# Loop_Schematic_r1_0_easyeda.net
KiCad netlist of a schematic drawn in EasyEDA
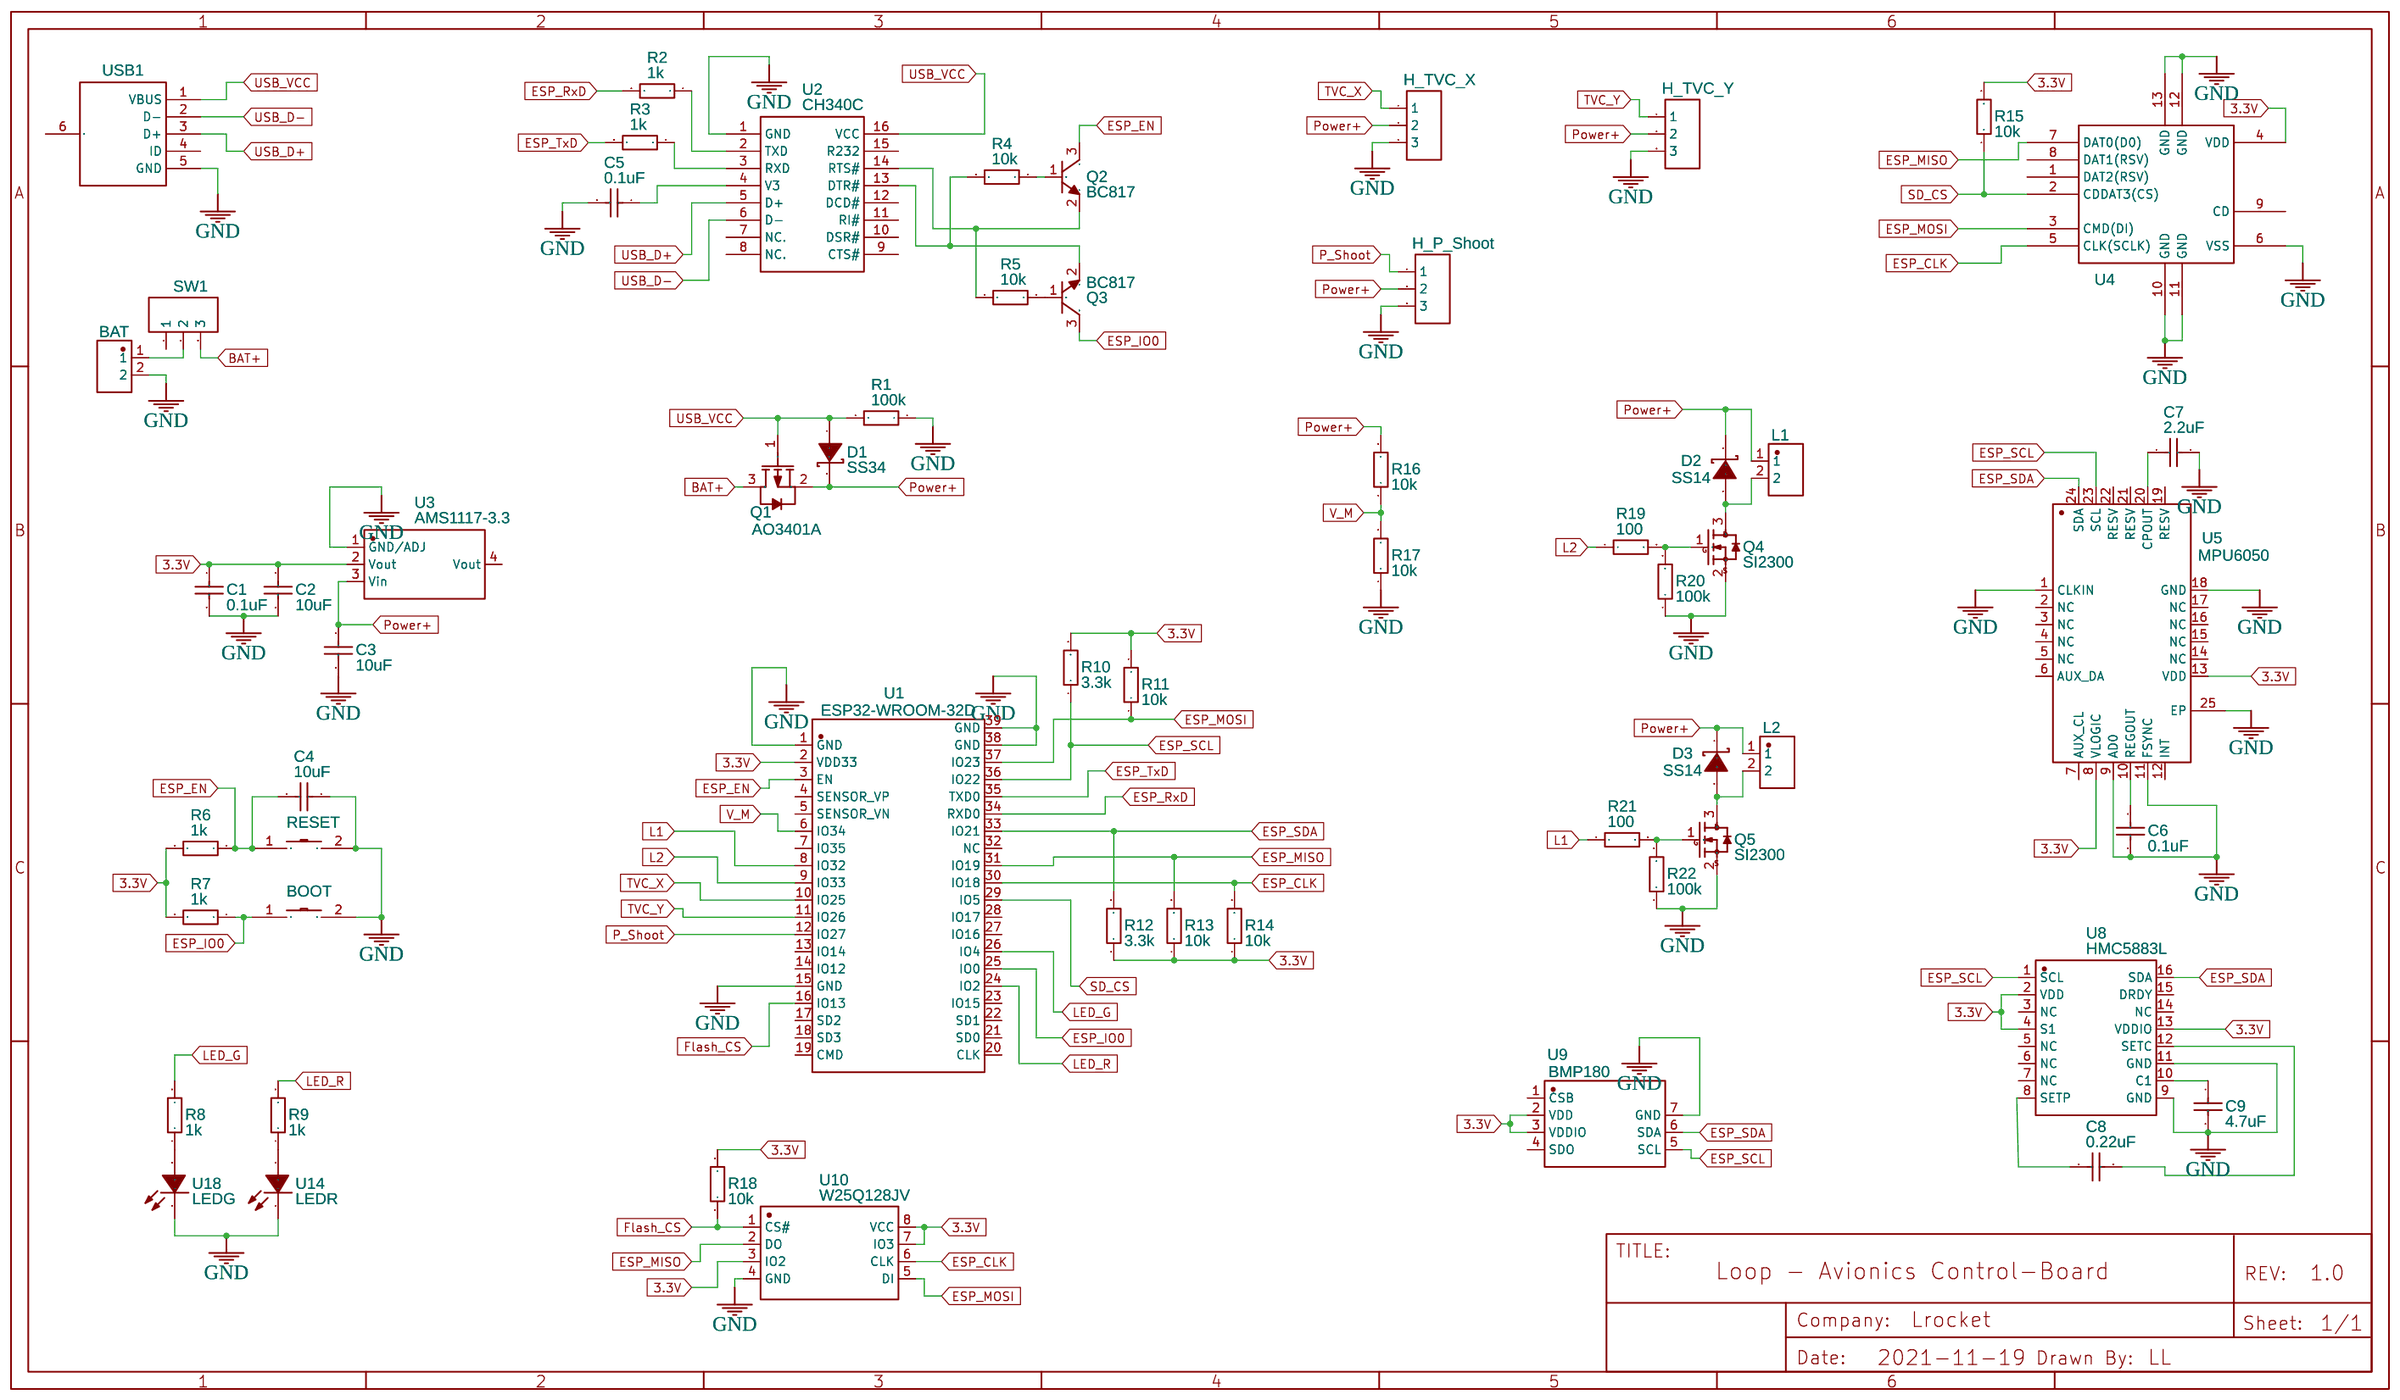
[diagram p0: schematic sheet]

(export (version "E")
  (design (tool "Eeschema 10.0.6"))
  (components
    (comp (ref "BAT")
      (value "BAT")
      (fields
        (field (name "BOM_Manufacturer Part") "KF128-5.08-2P")
        (field (name "BOM_Supplier Part") "C474952")
      )
      (libsource (lib "") (part "KF128-5.08-2P_1"))
    )
    (comp (ref "BOOT")
      (value "TS-1101-C-W")
      (fields (field (name "BOM_Supplier Part") "C318938"))
      (libsource (lib "") (part "TS-1101-C-W_1"))
    )
    (comp (ref "C1")
      (value "0.1uF")
      (fields
        (field (name "BOM_Manufacturer Part") "CC0603KRX7R9BB103")
        (field (name "BOM_Supplier Part") "C100042")
      )
      (libsource (lib "") (part "CC0603KRX7R9BB103"))
    )
    (comp (ref "C2")
      (value "10uF")
      (fields
        (field (name "BOM_Manufacturer Part") "CC0603KRX7R9BB103")
        (field (name "BOM_Supplier Part") "C100042")
      )
      (libsource (lib "") (part "CC0603KRX7R9BB103"))
    )
    (comp (ref "C3")
      (value "10uF")
      (fields
        (field (name "BOM_Manufacturer Part") "CC0603KRX7R9BB103")
        (field (name "BOM_Supplier Part") "C100042")
      )
      (libsource (lib "") (part "CC0603KRX7R9BB103"))
    )
    (comp (ref "C4")
      (value "10uF")
      (fields
        (field (name "BOM_Manufacturer Part") "CC0603KRX7R9BB103")
        (field (name "BOM_Supplier Part") "C100042")
      )
      (libsource (lib "") (part "CC0603KRX7R9BB103_1"))
    )
    (comp (ref "C5")
      (value "0.1uF")
      (fields
        (field (name "BOM_Manufacturer Part") "CC0603KRX7R9BB103")
        (field (name "BOM_Supplier Part") "C100042")
      )
      (libsource (lib "") (part "CC0603KRX7R9BB103_1"))
    )
    (comp (ref "C6")
      (value "0.1uF")
      (fields
        (field (name "BOM_Manufacturer Part") "CC0603KRX7R9BB103")
        (field (name "BOM_Supplier Part") "C100042")
      )
      (libsource (lib "") (part "CC0603KRX7R9BB103_2"))
    )
    (comp (ref "C7")
      (value "2.2uF")
      (fields
        (field (name "BOM_Manufacturer Part") "CC0603KRX7R9BB103")
        (field (name "BOM_Supplier Part") "C100042")
      )
      (libsource (lib "") (part "CC0603KRX7R9BB103_3"))
    )
    (comp (ref "C8")
      (value "0.22uF")
      (fields
        (field (name "BOM_Manufacturer Part") "CC0603KRX7R9BB103")
        (field (name "BOM_Supplier Part") "C100042")
      )
      (libsource (lib "") (part "CC0603KRX7R9BB103_3"))
    )
    (comp (ref "C9")
      (value "4.7uF")
      (fields
        (field (name "BOM_Manufacturer Part") "CC0603KRX7R9BB103")
        (field (name "BOM_Supplier Part") "C100042")
      )
      (libsource (lib "") (part "CC0603KRX7R9BB103"))
    )
    (comp (ref "D1")
      (value "SS34")
      (fields (field (name "BOM_Supplier Part") "C13763"))
      (libsource (lib "") (part "SS34"))
    )
    (comp (ref "D2")
      (value "SS14")
      (fields (field (name "BOM_Supplier Part") "C2480"))
      (libsource (lib "") (part "SS14"))
    )
    (comp (ref "D3")
      (value "SS14")
      (fields (field (name "BOM_Supplier Part") "C2480"))
      (libsource (lib "") (part "SS14"))
    )
    (comp (ref "L1")
      (value "L1")
      (fields
        (field (name "BOM_Manufacturer Part") "KF128-5.08-2P")
        (field (name "BOM_Supplier Part") "C474952")
      )
      (libsource (lib "") (part "KF128-5.08-2P"))
    )
    (comp (ref "L2")
      (value "KF128-5.08-2P")
      (fields (field (name "BOM_Supplier Part") "C474952"))
      (libsource (lib "") (part "KF128-5.08-2P"))
    )
    (comp (ref "P_SHOOT")
      (value "H_P_Shoot")
      (fields
        (field (name "BOM_Manufacturer Part") "Header2.54mm 1*3P")
        (field (name "BOM_Supplier Part") "C49257")
      )
      (libsource (lib "") (part "Header-Male-2.54_1x3"))
    )
    (comp (ref "Q1")
      (value "AO3401A")
      (fields (field (name "BOM_Supplier Part") "C15127"))
      (libsource (lib "") (part "AO3401A"))
    )
    (comp (ref "Q2")
      (value "BC817")
      (fields (field (name "BOM_Manufacturer Part") "BC817-25") (field (name "BOM_Supplier Part") "C8588"))
      (libsource (lib "") (part "BC817-25_1"))
    )
    (comp (ref "Q3")
      (value "BC817")
      (fields (field (name "BOM_Manufacturer Part") "BC817-25") (field (name "BOM_Supplier Part") "C8588"))
      (libsource (lib "") (part "BC817-25"))
    )
    (comp (ref "Q4")
      (value "SI2300")
      (fields (field (name "BOM_Supplier Part") "C181085"))
      (libsource (lib "") (part "SI2300"))
    )
    (comp (ref "Q5")
      (value "SI2300")
      (fields (field (name "BOM_Supplier Part") "C181085"))
      (libsource (lib "") (part "SI2300"))
    )
    (comp (ref "R1")
      (value "100k")
      (fields
        (field (name "BOM_Manufacturer Part") "TR0603B10KP05250.1W")
        (field (name "BOM_Supplier Part") "C188363")
      )
      (libsource (lib "") (part "TR0603B10KP05250.1W_1"))
    )
    (comp (ref "R2")
      (value "1k")
      (fields
        (field (name "BOM_Manufacturer Part") "TR0603B10KP05250.1W")
        (field (name "BOM_Supplier Part") "C188363")
      )
      (libsource (lib "") (part "TR0603B10KP05250.1W_1"))
    )
    (comp (ref "R3")
      (value "1k")
      (fields
        (field (name "BOM_Manufacturer Part") "TR0603B10KP05250.1W")
        (field (name "BOM_Supplier Part") "C188363")
      )
      (libsource (lib "") (part "TR0603B10KP05250.1W_1"))
    )
    (comp (ref "R4")
      (value "10k")
      (fields
        (field (name "BOM_Manufacturer Part") "TR0603B10KP05250.1W")
        (field (name "BOM_Supplier Part") "C188363")
      )
      (libsource (lib "") (part "TR0603B10KP05250.1W_1"))
    )
    (comp (ref "R5")
      (value "10k")
      (fields
        (field (name "BOM_Manufacturer Part") "TR0603B10KP05250.1W")
        (field (name "BOM_Supplier Part") "C188363")
      )
      (libsource (lib "") (part "TR0603B10KP05250.1W_1"))
    )
    (comp (ref "R6")
      (value "1k")
      (fields
        (field (name "BOM_Manufacturer Part") "TR0603B10KP05250.1W")
        (field (name "BOM_Supplier Part") "C188363")
      )
      (libsource (lib "") (part "TR0603B10KP05250.1W_1"))
    )
    (comp (ref "R7")
      (value "1k")
      (fields
        (field (name "BOM_Manufacturer Part") "TR0603B10KP05250.1W")
        (field (name "BOM_Supplier Part") "C188363")
      )
      (libsource (lib "") (part "TR0603B10KP05250.1W_1"))
    )
    (comp (ref "R8")
      (value "1k")
      (fields
        (field (name "BOM_Manufacturer Part") "TR0603B10KP05250.1W")
        (field (name "BOM_Supplier Part") "C188363")
      )
      (libsource (lib "") (part "TR0603B10KP05250.1W"))
    )
    (comp (ref "R9")
      (value "1k")
      (fields
        (field (name "BOM_Manufacturer Part") "TR0603B10KP05250.1W")
        (field (name "BOM_Supplier Part") "C188363")
      )
      (libsource (lib "") (part "TR0603B10KP05250.1W"))
    )
    (comp (ref "R10")
      (value "3.3k")
      (fields
        (field (name "BOM_Manufacturer Part") "TR0603B10KP05250.1W")
        (field (name "BOM_Supplier Part") "C188363")
      )
      (libsource (lib "") (part "TR0603B10KP05250.1W"))
    )
    (comp (ref "R11")
      (value "10k")
      (fields
        (field (name "BOM_Manufacturer Part") "TR0603B10KP05250.1W")
        (field (name "BOM_Supplier Part") "C188363")
      )
      (libsource (lib "") (part "TR0603B10KP05250.1W"))
    )
    (comp (ref "R12")
      (value "3.3k")
      (fields
        (field (name "BOM_Manufacturer Part") "TR0603B10KP05250.1W")
        (field (name "BOM_Supplier Part") "C188363")
      )
      (libsource (lib "") (part "TR0603B10KP05250.1W"))
    )
    (comp (ref "R13")
      (value "10k")
      (fields
        (field (name "BOM_Manufacturer Part") "TR0603B10KP05250.1W")
        (field (name "BOM_Supplier Part") "C188363")
      )
      (libsource (lib "") (part "TR0603B10KP05250.1W"))
    )
    (comp (ref "R14")
      (value "10k")
      (fields
        (field (name "BOM_Manufacturer Part") "TR0603B10KP05250.1W")
        (field (name "BOM_Supplier Part") "C188363")
      )
      (libsource (lib "") (part "TR0603B10KP05250.1W"))
    )
    (comp (ref "R15")
      (value "10k")
      (fields
        (field (name "BOM_Manufacturer Part") "TR0603B10KP05250.1W")
        (field (name "BOM_Supplier Part") "C188363")
      )
      (libsource (lib "") (part "TR0603B10KP05250.1W"))
    )
    (comp (ref "R16")
      (value "10k")
      (fields
        (field (name "BOM_Manufacturer Part") "TR0603B10KP05250.1W")
        (field (name "BOM_Supplier Part") "C188363")
      )
      (libsource (lib "") (part "TR0603B10KP05250.1W"))
    )
    (comp (ref "R17")
      (value "10k")
      (fields
        (field (name "BOM_Manufacturer Part") "TR0603B10KP05250.1W")
        (field (name "BOM_Supplier Part") "C188363")
      )
      (libsource (lib "") (part "TR0603B10KP05250.1W"))
    )
    (comp (ref "R18")
      (value "10k")
      (fields
        (field (name "BOM_Manufacturer Part") "TR0603B10KP05250.1W")
        (field (name "BOM_Supplier Part") "C188363")
      )
      (libsource (lib "") (part "TR0603B10KP05250.1W"))
    )
    (comp (ref "R19")
      (value "100")
      (fields
        (field (name "BOM_Manufacturer Part") "TR0603B10KP05250.1W")
        (field (name "BOM_Supplier Part") "C188363")
      )
      (libsource (lib "") (part "TR0603B10KP05250.1W_2"))
    )
    (comp (ref "R20")
      (value "100k")
      (fields
        (field (name "BOM_Manufacturer Part") "TR0603B10KP05250.1W")
        (field (name "BOM_Supplier Part") "C188363")
      )
      (libsource (lib "") (part "TR0603B10KP05250.1W"))
    )
    (comp (ref "R21")
      (value "100")
      (fields
        (field (name "BOM_Manufacturer Part") "TR0603B10KP05250.1W")
        (field (name "BOM_Supplier Part") "C188363")
      )
      (libsource (lib "") (part "TR0603B10KP05250.1W_2"))
    )
    (comp (ref "R22")
      (value "100k")
      (fields
        (field (name "BOM_Manufacturer Part") "TR0603B10KP05250.1W")
        (field (name "BOM_Supplier Part") "C188363")
      )
      (libsource (lib "") (part "TR0603B10KP05250.1W"))
    )
    (comp (ref "RESET")
      (value "TS-1101-C-W")
      (fields (field (name "BOM_Supplier Part") "C318938"))
      (libsource (lib "") (part "TS-1101-C-W"))
    )
    (comp (ref "SW1")
      (value "SW1")
      (fields
        (field (name "BOM_Manufacturer Part") "Header2.54mm 1*3P")
        (field (name "BOM_Supplier Part") "C49257")
      )
      (libsource (lib "") (part "Header-Male-2.54_1x3_1"))
    )
    (comp (ref "TVC_X")
      (value "H_TVC_X")
      (fields
        (field (name "BOM_Manufacturer Part") "Header2.54mm 1*3P")
        (field (name "BOM_Supplier Part") "C49257")
      )
      (libsource (lib "") (part "Header-Male-2.54_1x3_2"))
    )
    (comp (ref "TVC_Y")
      (value "H_TVC_Y")
      (fields
        (field (name "BOM_Manufacturer Part") "Header2.54mm 1*3P")
        (field (name "BOM_Supplier Part") "C49257")
      )
      (libsource (lib "") (part "Header-Male-2.54_1x3_3"))
    )
    (comp (ref "U1")
      (value "ESP32-WROOM-32D")
      (fields (field (name "BOM_Supplier Part") "C473012"))
      (libsource (lib "") (part "ESP32-WROOM-32D"))
    )
    (comp (ref "U2")
      (value "CH340C")
      (fields (field (name "BOM_Supplier Part") "C84681"))
      (libsource (lib "") (part "CH340C"))
    )
    (comp (ref "U3")
      (value "AMS1117-3.3")
      (fields (field (name "BOM_Supplier Part") "C6186"))
      (libsource (lib "") (part "AMS1117-3.3"))
    )
    (comp (ref "U4")
      (value "TF-01A")
      (fields (field (name "BOM_Supplier Part") "C91145"))
      (libsource (lib "") (part "TF-01A"))
    )
    (comp (ref "U5")
      (value "MPU6050")
      (fields
        (field (name "BOM_Manufacturer Part") "MPU6050-YJLTY")
        (field (name "BOM_Supplier Part") "C2912107")
      )
      (libsource (lib "") (part "MPU6050-YJLTY"))
    )
    (comp (ref "U8")
      (value "HMC5883L")
      (fields (field (name "BOM_Supplier Part") "C2859540"))
      (libsource (lib "") (part "HMC5883L"))
    )
    (comp (ref "U9")
      (value "BMP180")
      (fields (field (name "BOM_Supplier Part") "C438474"))
      (libsource (lib "") (part "BMP180"))
    )
    (comp (ref "U10")
      (value "W25Q128JV")
      (fields
        (field (name "BOM_Manufacturer Part") "W25Q128JVSIQTR")
        (field (name "BOM_Supplier Part") "C97521")
      )
      (libsource (lib "") (part "W25Q128JVSIQTR"))
    )
    (comp (ref "U14")
      (value "LEDR")
      (fields (field (name "BOM_Manufacturer Part") "SZYY0603W") (field (name "BOM_Supplier Part") "C434422"))
      (libsource (lib "") (part "SZYY0603W"))
    )
    (comp (ref "U18")
      (value "LEDG")
      (fields (field (name "BOM_Manufacturer Part") "SZYY0603W") (field (name "BOM_Supplier Part") "C434422"))
      (libsource (lib "") (part "SZYY0603W"))
    )
    (comp (ref "USB1")
      (value "USB1")
      (fields
        (field (name "BOM_Manufacturer Part") "U254-051T-4BH83-S1S")
        (field (name "BOM_Supplier Part") "C319160")
      )
      (libsource (lib "") (part "U254-051T-4BH83-S1S"))
    )
  )
  (nets
    (net (code "1") (name "3.3V") (class "Default")
      (node (ref "C1") (pin "1") (pinfunction "1_1") (pintype "input"))
      (node (ref "C2") (pin "1") (pinfunction "1_1") (pintype "input"))
      (node (ref "R10") (pin "2") (pinfunction "2_2") (pintype "unspecified"))
      (node (ref "R11") (pin "2") (pinfunction "2_2") (pintype "unspecified"))
      (node (ref "R12") (pin "1") (pinfunction "1_1") (pintype "unspecified"))
      (node (ref "R13") (pin "1") (pinfunction "1_1") (pintype "unspecified"))
      (node (ref "R14") (pin "1") (pinfunction "1_1") (pintype "unspecified"))
      (node (ref "R15") (pin "2") (pinfunction "2_2") (pintype "unspecified"))
      (node (ref "R18") (pin "2") (pinfunction "2_2") (pintype "unspecified"))
      (node (ref "R6") (pin "2") (pinfunction "2_2") (pintype "unspecified"))
      (node (ref "R7") (pin "2") (pinfunction "2_2") (pintype "unspecified"))
      (node (ref "U1") (pin "2") (pinfunction "VDD33_2") (pintype "unspecified"))
      (node (ref "U10") (pin "3") (pinfunction "IO2_3") (pintype "unspecified"))
      (node (ref "U10") (pin "7") (pinfunction "IO3_7") (pintype "unspecified"))
      (node (ref "U10") (pin "8") (pinfunction "VCC_8") (pintype "unspecified"))
      (node (ref "U3") (pin "2") (pinfunction "Vout_2") (pintype "unspecified"))
      (node (ref "U4") (pin "4") (pinfunction "VDD_4") (pintype "input"))
      (node (ref "U5") (pin "13") (pinfunction "VDD_13") (pintype "unspecified"))
      (node (ref "U5") (pin "8") (pinfunction "VLOGIC_8") (pintype "unspecified"))
      (node (ref "U8") (pin "13") (pinfunction "VDDIO_13") (pintype "unspecified"))
      (node (ref "U8") (pin "2") (pinfunction "VDD_2") (pintype "unspecified"))
      (node (ref "U8") (pin "4") (pinfunction "S1_4") (pintype "unspecified"))
      (node (ref "U9") (pin "2") (pinfunction "VDD_2") (pintype "unspecified"))
      (node (ref "U9") (pin "3") (pinfunction "VDDIO_3") (pintype "unspecified"))
    )
    (net (code "2") (name "BAT+") (class "Default")
      (node (ref "Q1") (pin "3") (pinfunction "D_3") (pintype "unspecified"))
      (node (ref "SW1") (pin "3") (pinfunction "3_3") (pintype "input"))
    )
    (net (code "3") (name "ESP_CLK") (class "Default")
      (node (ref "R14") (pin "2") (pinfunction "2_2") (pintype "unspecified"))
      (node (ref "U1") (pin "30") (pinfunction "IO18_30") (pintype "unspecified"))
      (node (ref "U10") (pin "6") (pinfunction "CLK_6") (pintype "unspecified"))
      (node (ref "U4") (pin "5") (pinfunction "CLK(SCLK)_5") (pintype "input"))
    )
    (net (code "4") (name "ESP_EN") (class "Default")
      (node (ref "C4") (pin "2") (pinfunction "2_2") (pintype "input"))
      (node (ref "Q2") (pin "3") (pinfunction "C_3") (pintype "unspecified"))
      (node (ref "R6") (pin "1") (pinfunction "1_1") (pintype "unspecified"))
      (node (ref "RESET") (pin "1") (pinfunction "1_1") (pintype "unspecified"))
      (node (ref "U1") (pin "3") (pinfunction "EN_3") (pintype "unspecified"))
    )
    (net (code "5") (name "ESP_IO0") (class "Default")
      (node (ref "BOOT") (pin "1") (pinfunction "1_1") (pintype "unspecified"))
      (node (ref "Q3") (pin "3") (pinfunction "C_3") (pintype "unspecified"))
      (node (ref "R7") (pin "1") (pinfunction "1_1") (pintype "unspecified"))
      (node (ref "U1") (pin "25") (pinfunction "IO0_25") (pintype "unspecified"))
    )
    (net (code "6") (name "ESP_MISO") (class "Default")
      (node (ref "R13") (pin "2") (pinfunction "2_2") (pintype "unspecified"))
      (node (ref "U1") (pin "31") (pinfunction "IO19_31") (pintype "unspecified"))
      (node (ref "U10") (pin "2") (pinfunction "DO_2") (pintype "unspecified"))
      (node (ref "U4") (pin "7") (pinfunction "DAT0(D0)_7") (pintype "bidirectional"))
    )
    (net (code "7") (name "ESP_MOSI") (class "Default")
      (node (ref "R11") (pin "1") (pinfunction "1_1") (pintype "unspecified"))
      (node (ref "U1") (pin "37") (pinfunction "IO23_37") (pintype "unspecified"))
      (node (ref "U10") (pin "5") (pinfunction "DI_5") (pintype "unspecified"))
      (node (ref "U4") (pin "3") (pinfunction "CMD(DI)_3") (pintype "input"))
    )
    (net (code "8") (name "ESP_RxD") (class "Default")
      (node (ref "R2") (pin "2") (pinfunction "2_2") (pintype "unspecified"))
      (node (ref "U1") (pin "34") (pinfunction "RXD0_34") (pintype "unspecified"))
    )
    (net (code "9") (name "ESP_SCL") (class "Default")
      (node (ref "R10") (pin "1") (pinfunction "1_1") (pintype "unspecified"))
      (node (ref "U1") (pin "36") (pinfunction "IO22_36") (pintype "unspecified"))
      (node (ref "U5") (pin "23") (pinfunction "SCL_23") (pintype "unspecified"))
      (node (ref "U8") (pin "1") (pinfunction "SCL_1") (pintype "unspecified"))
      (node (ref "U9") (pin "5") (pinfunction "SCL_5") (pintype "unspecified"))
    )
    (net (code "10") (name "ESP_SDA") (class "Default")
      (node (ref "R12") (pin "2") (pinfunction "2_2") (pintype "unspecified"))
      (node (ref "U1") (pin "33") (pinfunction "IO21_33") (pintype "unspecified"))
      (node (ref "U5") (pin "24") (pinfunction "SDA_24") (pintype "unspecified"))
      (node (ref "U8") (pin "16") (pinfunction "SDA_16") (pintype "unspecified"))
      (node (ref "U9") (pin "6") (pinfunction "SDA_6") (pintype "unspecified"))
    )
    (net (code "11") (name "ESP_TxD") (class "Default")
      (node (ref "R3") (pin "2") (pinfunction "2_2") (pintype "unspecified"))
      (node (ref "U1") (pin "35") (pinfunction "TXD0_35") (pintype "unspecified"))
    )
    (net (code "12") (name "Flash_CS") (class "Default")
      (node (ref "R18") (pin "1") (pinfunction "1_1") (pintype "unspecified"))
      (node (ref "U1") (pin "16") (pinfunction "IO13_16") (pintype "unspecified"))
      (node (ref "U10") (pin "1") (pinfunction "CS#_1") (pintype "unspecified"))
    )
    (net (code "13") (name "GND") (class "Default")
      (node (ref "BAT") (pin "2") (pinfunction "2_2") (pintype "unspecified"))
      (node (ref "BOOT") (pin "2") (pinfunction "2_2") (pintype "unspecified"))
      (node (ref "C1") (pin "2") (pinfunction "2_2") (pintype "input"))
      (node (ref "C2") (pin "2") (pinfunction "2_2") (pintype "input"))
      (node (ref "C3") (pin "2") (pinfunction "2_2") (pintype "input"))
      (node (ref "C4") (pin "1") (pinfunction "1_1") (pintype "input"))
      (node (ref "C5") (pin "2") (pinfunction "2_2") (pintype "input"))
      (node (ref "C6") (pin "1") (pinfunction "1_1") (pintype "input"))
      (node (ref "C7") (pin "2") (pinfunction "2_2") (pintype "input"))
      (node (ref "C9") (pin "2") (pinfunction "2_2") (pintype "input"))
      (node (ref "P_SHOOT") (pin "3") (pinfunction "3_3") (pintype "input"))
      (node (ref "Q4") (pin "2") (pinfunction "S_2") (pintype "unspecified"))
      (node (ref "Q5") (pin "2") (pinfunction "S_2") (pintype "unspecified"))
      (node (ref "R1") (pin "1") (pinfunction "1_1") (pintype "unspecified"))
      (node (ref "R17") (pin "1") (pinfunction "1_1") (pintype "unspecified"))
      (node (ref "R20") (pin "1") (pinfunction "1_1") (pintype "unspecified"))
      (node (ref "R22") (pin "1") (pinfunction "1_1") (pintype "unspecified"))
      (node (ref "RESET") (pin "2") (pinfunction "2_2") (pintype "unspecified"))
      (node (ref "TVC_X") (pin "3") (pinfunction "3_3") (pintype "input"))
      (node (ref "TVC_Y") (pin "3") (pinfunction "3_3") (pintype "input"))
      (node (ref "U1") (pin "1") (pinfunction "GND_1") (pintype "unspecified"))
      (node (ref "U1") (pin "15") (pinfunction "GND_15") (pintype "unspecified"))
      (node (ref "U1") (pin "38") (pinfunction "GND_38") (pintype "unspecified"))
      (node (ref "U1") (pin "39") (pinfunction "GND_39") (pintype "unspecified"))
      (node (ref "U10") (pin "4") (pinfunction "GND_4") (pintype "unspecified"))
      (node (ref "U14") (pin "2") (pinfunction "-_2") (pintype "unspecified"))
      (node (ref "U18") (pin "2") (pinfunction "-_2") (pintype "unspecified"))
      (node (ref "U2") (pin "1") (pinfunction "GND_1") (pintype "unspecified"))
      (node (ref "U3") (pin "1") (pinfunction "GND/ADJ_1") (pintype "unspecified"))
      (node (ref "U4") (pin "10") (pinfunction "GND_10") (pintype "input"))
      (node (ref "U4") (pin "11") (pinfunction "GND_11") (pintype "input"))
      (node (ref "U4") (pin "12") (pinfunction "GND_12") (pintype "input"))
      (node (ref "U4") (pin "13") (pinfunction "GND_13") (pintype "input"))
      (node (ref "U4") (pin "6") (pinfunction "VSS_6") (pintype "input"))
      (node (ref "U5") (pin "1") (pinfunction "CLKIN_1") (pintype "unspecified"))
      (node (ref "U5") (pin "11") (pinfunction "FSYNC_11") (pintype "unspecified"))
      (node (ref "U5") (pin "18") (pinfunction "GND_18") (pintype "unspecified"))
      (node (ref "U5") (pin "25") (pinfunction "EP_25") (pintype "unspecified"))
      (node (ref "U5") (pin "9") (pinfunction "AD0_9") (pintype "unspecified"))
      (node (ref "U8") (pin "11") (pinfunction "GND_11") (pintype "unspecified"))
      (node (ref "U8") (pin "9") (pinfunction "GND_9") (pintype "unspecified"))
      (node (ref "U9") (pin "7") (pinfunction "GND_7") (pintype "unspecified"))
      (node (ref "USB1") (pin "5") (pinfunction "GND_5") (pintype "input"))
    )
    (net (code "14") (name "L1") (class "Default")
      (node (ref "R21") (pin "1") (pinfunction "1_1") (pintype "unspecified"))
      (node (ref "U1") (pin "8") (pinfunction "IO32_8") (pintype "unspecified"))
    )
    (net (code "15") (name "L2") (class "Default")
      (node (ref "R19") (pin "1") (pinfunction "1_1") (pintype "unspecified"))
      (node (ref "U1") (pin "9") (pinfunction "IO33_9") (pintype "unspecified"))
    )
    (net (code "16") (name "LED_G") (class "Default")
      (node (ref "R8") (pin "2") (pinfunction "2_2") (pintype "unspecified"))
      (node (ref "U1") (pin "26") (pinfunction "IO4_26") (pintype "unspecified"))
    )
    (net (code "17") (name "LED_R") (class "Default")
      (node (ref "R9") (pin "2") (pinfunction "2_2") (pintype "unspecified"))
      (node (ref "U1") (pin "24") (pinfunction "IO2_24") (pintype "unspecified"))
    )
    (net (code "18") (name "Net-(BAT-Pad1)") (class "Default")
      (node (ref "BAT") (pin "1") (pinfunction "1_1") (pintype "unspecified"))
      (node (ref "SW1") (pin "2") (pinfunction "2_2") (pintype "input"))
    )
    (net (code "19") (name "Net-(D2-A)") (class "Default")
      (node (ref "D2") (pin "2") (pinfunction "A_2") (pintype "unspecified"))
      (node (ref "L1") (pin "2") (pinfunction "2_2") (pintype "unspecified"))
      (node (ref "Q4") (pin "3") (pinfunction "D_3") (pintype "unspecified"))
    )
    (net (code "20") (name "Net-(D3-A)") (class "Default")
      (node (ref "D3") (pin "2") (pinfunction "A_2") (pintype "unspecified"))
      (node (ref "L2") (pin "2") (pinfunction "2_2") (pintype "unspecified"))
      (node (ref "Q5") (pin "3") (pinfunction "D_3") (pintype "unspecified"))
    )
    (net (code "21") (name "Net-(Q2-B)") (class "Default")
      (node (ref "Q2") (pin "1") (pinfunction "B_1") (pintype "unspecified"))
      (node (ref "R4") (pin "1") (pinfunction "1_1") (pintype "unspecified"))
    )
    (net (code "22") (name "Net-(Q2-E)") (class "Default")
      (node (ref "Q2") (pin "2") (pinfunction "E_2") (pintype "unspecified"))
      (node (ref "R5") (pin "2") (pinfunction "2_2") (pintype "unspecified"))
      (node (ref "U2") (pin "14") (pinfunction "RTS#_14") (pintype "unspecified"))
    )
    (net (code "23") (name "Net-(Q3-B)") (class "Default")
      (node (ref "Q3") (pin "1") (pinfunction "B_1") (pintype "unspecified"))
      (node (ref "R5") (pin "1") (pinfunction "1_1") (pintype "unspecified"))
    )
    (net (code "24") (name "Net-(Q3-E)") (class "Default")
      (node (ref "Q3") (pin "2") (pinfunction "E_2") (pintype "unspecified"))
      (node (ref "R4") (pin "2") (pinfunction "2_2") (pintype "unspecified"))
      (node (ref "U2") (pin "13") (pinfunction "DTR#_13") (pintype "unspecified"))
    )
    (net (code "25") (name "Net-(Q4-G)") (class "Default")
      (node (ref "Q4") (pin "1") (pinfunction "G_1") (pintype "unspecified"))
      (node (ref "R19") (pin "2") (pinfunction "2_2") (pintype "unspecified"))
      (node (ref "R20") (pin "2") (pinfunction "2_2") (pintype "unspecified"))
    )
    (net (code "26") (name "Net-(Q5-G)") (class "Default")
      (node (ref "Q5") (pin "1") (pinfunction "G_1") (pintype "unspecified"))
      (node (ref "R21") (pin "2") (pinfunction "2_2") (pintype "unspecified"))
      (node (ref "R22") (pin "2") (pinfunction "2_2") (pintype "unspecified"))
    )
    (net (code "27") (name "Net-(U2-RXD)") (class "Default")
      (node (ref "R3") (pin "1") (pinfunction "1_1") (pintype "unspecified"))
      (node (ref "U2") (pin "3") (pinfunction "RXD_3") (pintype "unspecified"))
    )
    (net (code "28") (name "Net-(U2-TXD)") (class "Default")
      (node (ref "R2") (pin "1") (pinfunction "1_1") (pintype "unspecified"))
      (node (ref "U2") (pin "2") (pinfunction "TXD_2") (pintype "unspecified"))
    )
    (net (code "29") (name "Net-(U2-V3)") (class "Default")
      (node (ref "C5") (pin "1") (pinfunction "1_1") (pintype "input"))
      (node (ref "U2") (pin "4") (pinfunction "V3_4") (pintype "unspecified"))
    )
    (net (code "30") (name "Net-(U5-CPOUT)") (class "Default")
      (node (ref "C7") (pin "1") (pinfunction "1_1") (pintype "input"))
      (node (ref "U5") (pin "20") (pinfunction "CPOUT_20") (pintype "unspecified"))
    )
    (net (code "31") (name "Net-(U5-REGOUT)") (class "Default")
      (node (ref "C6") (pin "2") (pinfunction "2_2") (pintype "input"))
      (node (ref "U5") (pin "10") (pinfunction "REGOUT_10") (pintype "unspecified"))
    )
    (net (code "32") (name "Net-(U8-C1)") (class "Default")
      (node (ref "C9") (pin "1") (pinfunction "1_1") (pintype "input"))
      (node (ref "U8") (pin "10") (pinfunction "C1_10") (pintype "unspecified"))
    )
    (net (code "33") (name "Net-(U8-SETC)") (class "Default")
      (node (ref "C8") (pin "2") (pinfunction "2_2") (pintype "input"))
      (node (ref "U8") (pin "12") (pinfunction "SETC_12") (pintype "unspecified"))
    )
    (net (code "34") (name "Net-(U8-SETP)") (class "Default")
      (node (ref "C8") (pin "1") (pinfunction "1_1") (pintype "input"))
      (node (ref "U8") (pin "8") (pinfunction "SETP_8") (pintype "unspecified"))
    )
    (net (code "35") (name "Net-(U14-+)") (class "Default")
      (node (ref "R9") (pin "1") (pinfunction "1_1") (pintype "unspecified"))
      (node (ref "U14") (pin "1") (pinfunction "+_1") (pintype "unspecified"))
    )
    (net (code "36") (name "Net-(U18-+)") (class "Default")
      (node (ref "R8") (pin "1") (pinfunction "1_1") (pintype "unspecified"))
      (node (ref "U18") (pin "1") (pinfunction "+_1") (pintype "unspecified"))
    )
    (net (code "37") (name "P_Shoot") (class "Default")
      (node (ref "P_SHOOT") (pin "1") (pinfunction "1_1") (pintype "input"))
      (node (ref "U1") (pin "12") (pinfunction "IO27_12") (pintype "unspecified"))
    )
    (net (code "38") (name "Power+") (class "Default")
      (node (ref "C3") (pin "1") (pinfunction "1_1") (pintype "input"))
      (node (ref "D1") (pin "2") (pinfunction "K_2") (pintype "unspecified"))
      (node (ref "D2") (pin "1") (pinfunction "K_1") (pintype "unspecified"))
      (node (ref "D3") (pin "1") (pinfunction "K_1") (pintype "unspecified"))
      (node (ref "L1") (pin "1") (pinfunction "1_1") (pintype "unspecified"))
      (node (ref "L2") (pin "1") (pinfunction "1_1") (pintype "unspecified"))
      (node (ref "P_SHOOT") (pin "2") (pinfunction "2_2") (pintype "input"))
      (node (ref "Q1") (pin "2") (pinfunction "S_2") (pintype "unspecified"))
      (node (ref "R16") (pin "2") (pinfunction "2_2") (pintype "unspecified"))
      (node (ref "TVC_X") (pin "2") (pinfunction "2_2") (pintype "input"))
      (node (ref "TVC_Y") (pin "2") (pinfunction "2_2") (pintype "input"))
      (node (ref "U3") (pin "3") (pinfunction "Vin_3") (pintype "unspecified"))
    )
    (net (code "39") (name "SD_CS") (class "Default")
      (node (ref "R15") (pin "1") (pinfunction "1_1") (pintype "unspecified"))
      (node (ref "U1") (pin "29") (pinfunction "IO5_29") (pintype "unspecified"))
      (node (ref "U4") (pin "2") (pinfunction "CDDAT3(CS)_2") (pintype "bidirectional"))
    )
    (net (code "40") (name "TVC_X") (class "Default")
      (node (ref "TVC_X") (pin "1") (pinfunction "1_1") (pintype "input"))
      (node (ref "U1") (pin "10") (pinfunction "IO25_10") (pintype "unspecified"))
    )
    (net (code "41") (name "TVC_Y") (class "Default")
      (node (ref "TVC_Y") (pin "1") (pinfunction "1_1") (pintype "input"))
      (node (ref "U1") (pin "11") (pinfunction "IO26_11") (pintype "unspecified"))
    )
    (net (code "42") (name "USB_D+") (class "Default")
      (node (ref "U2") (pin "5") (pinfunction "D+_5") (pintype "unspecified"))
      (node (ref "USB1") (pin "3") (pinfunction "D+_3") (pintype "input"))
    )
    (net (code "43") (name "USB_D-") (class "Default")
      (node (ref "U2") (pin "6") (pinfunction "D-_6") (pintype "unspecified"))
      (node (ref "USB1") (pin "2") (pinfunction "D-_2") (pintype "input"))
    )
    (net (code "44") (name "USB_VCC") (class "Default")
      (node (ref "D1") (pin "1") (pinfunction "A_1") (pintype "unspecified"))
      (node (ref "Q1") (pin "1") (pinfunction "G_1") (pintype "unspecified"))
      (node (ref "R1") (pin "2") (pinfunction "2_2") (pintype "unspecified"))
      (node (ref "U2") (pin "16") (pinfunction "VCC_16") (pintype "unspecified"))
      (node (ref "USB1") (pin "1") (pinfunction "VBUS_1") (pintype "input"))
    )
    (net (code "45") (name "V_M") (class "Default")
      (node (ref "R16") (pin "1") (pinfunction "1_1") (pintype "unspecified"))
      (node (ref "R17") (pin "2") (pinfunction "2_2") (pintype "unspecified"))
      (node (ref "U1") (pin "6") (pinfunction "IO34_6") (pintype "unspecified"))
    )
    (net (code "46") (name "unconnected-(SW1-Pad1)") (class "Default")
      (node (ref "SW1") (pin "1") (pinfunction "1_1") (pintype "input"))
    )
    (net (code "47") (name "unconnected-(U1-CLK-Pad20)") (class "Default")
      (node (ref "U1") (pin "20") (pinfunction "CLK_20") (pintype "unspecified"))
    )
    (net (code "48") (name "unconnected-(U1-CMD-Pad19)") (class "Default")
      (node (ref "U1") (pin "19") (pinfunction "CMD_19") (pintype "unspecified"))
    )
    (net (code "49") (name "unconnected-(U1-IO12-Pad14)") (class "Default")
      (node (ref "U1") (pin "14") (pinfunction "IO12_14") (pintype "unspecified"))
    )
    (net (code "50") (name "unconnected-(U1-IO14-Pad13)") (class "Default")
      (node (ref "U1") (pin "13") (pinfunction "IO14_13") (pintype "unspecified"))
    )
    (net (code "51") (name "unconnected-(U1-IO15-Pad23)") (class "Default")
      (node (ref "U1") (pin "23") (pinfunction "IO15_23") (pintype "unspecified"))
    )
    (net (code "52") (name "unconnected-(U1-IO16-Pad27)") (class "Default")
      (node (ref "U1") (pin "27") (pinfunction "IO16_27") (pintype "unspecified"))
    )
    (net (code "53") (name "unconnected-(U1-IO17-Pad28)") (class "Default")
      (node (ref "U1") (pin "28") (pinfunction "IO17_28") (pintype "unspecified"))
    )
    (net (code "54") (name "unconnected-(U1-IO35-Pad7)") (class "Default")
      (node (ref "U1") (pin "7") (pinfunction "IO35_7") (pintype "unspecified"))
    )
    (net (code "55") (name "unconnected-(U1-NC-Pad32)") (class "Default")
      (node (ref "U1") (pin "32") (pinfunction "NC_32") (pintype "unspecified"))
    )
    (net (code "56") (name "unconnected-(U1-SD0-Pad21)") (class "Default")
      (node (ref "U1") (pin "21") (pinfunction "SD0_21") (pintype "unspecified"))
    )
    (net (code "57") (name "unconnected-(U1-SD1-Pad22)") (class "Default")
      (node (ref "U1") (pin "22") (pinfunction "SD1_22") (pintype "unspecified"))
    )
    (net (code "58") (name "unconnected-(U1-SD2-Pad17)") (class "Default")
      (node (ref "U1") (pin "17") (pinfunction "SD2_17") (pintype "unspecified"))
    )
    (net (code "59") (name "unconnected-(U1-SD3-Pad18)") (class "Default")
      (node (ref "U1") (pin "18") (pinfunction "SD3_18") (pintype "unspecified"))
    )
    (net (code "60") (name "unconnected-(U1-SENSOR_VN-Pad5)") (class "Default")
      (node (ref "U1") (pin "5") (pinfunction "SENSOR_VN_5") (pintype "unspecified"))
    )
    (net (code "61") (name "unconnected-(U1-SENSOR_VP-Pad4)") (class "Default")
      (node (ref "U1") (pin "4") (pinfunction "SENSOR_VP_4") (pintype "unspecified"))
    )
    (net (code "62") (name "unconnected-(U2-CTS#-Pad9)") (class "Default")
      (node (ref "U2") (pin "9") (pinfunction "CTS#_9") (pintype "unspecified"))
    )
    (net (code "63") (name "unconnected-(U2-DCD#-Pad12)") (class "Default")
      (node (ref "U2") (pin "12") (pinfunction "DCD#_12") (pintype "unspecified"))
    )
    (net (code "64") (name "unconnected-(U2-DSR#-Pad10)") (class "Default")
      (node (ref "U2") (pin "10") (pinfunction "DSR#_10") (pintype "unspecified"))
    )
    (net (code "65") (name "unconnected-(U2-NC.-Pad7)") (class "Default")
      (node (ref "U2") (pin "7") (pinfunction "NC._7") (pintype "unspecified"))
    )
    (net (code "66") (name "unconnected-(U2-NC.-Pad8)") (class "Default")
      (node (ref "U2") (pin "8") (pinfunction "NC._8") (pintype "unspecified"))
    )
    (net (code "67") (name "unconnected-(U2-R232-Pad15)") (class "Default")
      (node (ref "U2") (pin "15") (pinfunction "R232_15") (pintype "unspecified"))
    )
    (net (code "68") (name "unconnected-(U2-RI#-Pad11)") (class "Default")
      (node (ref "U2") (pin "11") (pinfunction "RI#_11") (pintype "unspecified"))
    )
    (net (code "69") (name "unconnected-(U3-Vout-Pad4)") (class "Default")
      (node (ref "U3") (pin "4") (pinfunction "Vout_4") (pintype "unspecified"))
    )
    (net (code "70") (name "unconnected-(U4-CD-Pad9)") (class "Default")
      (node (ref "U4") (pin "9") (pinfunction "CD_9") (pintype "input"))
    )
    (net (code "71") (name "unconnected-(U4-DAT1(RSV)-Pad8)") (class "Default")
      (node (ref "U4") (pin "8") (pinfunction "DAT1(RSV)_8") (pintype "bidirectional"))
    )
    (net (code "72") (name "unconnected-(U4-DAT2(RSV)-Pad1)") (class "Default")
      (node (ref "U4") (pin "1") (pinfunction "DAT2(RSV)_1") (pintype "bidirectional"))
    )
    (net (code "73") (name "unconnected-(U5-AUX_CL-Pad7)") (class "Default")
      (node (ref "U5") (pin "7") (pinfunction "AUX_CL_7") (pintype "unspecified"))
    )
    (net (code "74") (name "unconnected-(U5-AUX_DA-Pad6)") (class "Default")
      (node (ref "U5") (pin "6") (pinfunction "AUX_DA_6") (pintype "unspecified"))
    )
    (net (code "75") (name "unconnected-(U5-INT-Pad12)") (class "Default")
      (node (ref "U5") (pin "12") (pinfunction "INT_12") (pintype "unspecified"))
    )
    (net (code "76") (name "unconnected-(U5-NC-Pad2)") (class "Default")
      (node (ref "U5") (pin "2") (pinfunction "NC_2") (pintype "unspecified"))
    )
    (net (code "77") (name "unconnected-(U5-NC-Pad3)") (class "Default")
      (node (ref "U5") (pin "3") (pinfunction "NC_3") (pintype "unspecified"))
    )
    (net (code "78") (name "unconnected-(U5-NC-Pad4)") (class "Default")
      (node (ref "U5") (pin "4") (pinfunction "NC_4") (pintype "unspecified"))
    )
    (net (code "79") (name "unconnected-(U5-NC-Pad5)") (class "Default")
      (node (ref "U5") (pin "5") (pinfunction "NC_5") (pintype "unspecified"))
    )
    (net (code "80") (name "unconnected-(U5-NC-Pad14)") (class "Default")
      (node (ref "U5") (pin "14") (pinfunction "NC_14") (pintype "unspecified"))
    )
    (net (code "81") (name "unconnected-(U5-NC-Pad15)") (class "Default")
      (node (ref "U5") (pin "15") (pinfunction "NC_15") (pintype "unspecified"))
    )
    (net (code "82") (name "unconnected-(U5-NC-Pad16)") (class "Default")
      (node (ref "U5") (pin "16") (pinfunction "NC_16") (pintype "unspecified"))
    )
    (net (code "83") (name "unconnected-(U5-NC-Pad17)") (class "Default")
      (node (ref "U5") (pin "17") (pinfunction "NC_17") (pintype "unspecified"))
    )
    (net (code "84") (name "unconnected-(U5-RESV-Pad19)") (class "Default")
      (node (ref "U5") (pin "19") (pinfunction "RESV_19") (pintype "unspecified"))
    )
    (net (code "85") (name "unconnected-(U5-RESV-Pad21)") (class "Default")
      (node (ref "U5") (pin "21") (pinfunction "RESV_21") (pintype "unspecified"))
    )
    (net (code "86") (name "unconnected-(U5-RESV-Pad22)") (class "Default")
      (node (ref "U5") (pin "22") (pinfunction "RESV_22") (pintype "unspecified"))
    )
    (net (code "87") (name "unconnected-(U8-DRDY-Pad15)") (class "Default")
      (node (ref "U8") (pin "15") (pinfunction "DRDY_15") (pintype "unspecified"))
    )
    (net (code "88") (name "unconnected-(U8-NC-Pad3)") (class "Default")
      (node (ref "U8") (pin "3") (pinfunction "NC_3") (pintype "unspecified"))
    )
    (net (code "89") (name "unconnected-(U8-NC-Pad5)") (class "Default")
      (node (ref "U8") (pin "5") (pinfunction "NC_5") (pintype "unspecified"))
    )
    (net (code "90") (name "unconnected-(U8-NC-Pad6)") (class "Default")
      (node (ref "U8") (pin "6") (pinfunction "NC_6") (pintype "unspecified"))
    )
    (net (code "91") (name "unconnected-(U8-NC-Pad7)") (class "Default")
      (node (ref "U8") (pin "7") (pinfunction "NC_7") (pintype "unspecified"))
    )
    (net (code "92") (name "unconnected-(U8-NC-Pad14)") (class "Default")
      (node (ref "U8") (pin "14") (pinfunction "NC_14") (pintype "unspecified"))
    )
    (net (code "93") (name "unconnected-(U9-CSB-Pad1)") (class "Default")
      (node (ref "U9") (pin "1") (pinfunction "CSB_1") (pintype "unspecified"))
    )
    (net (code "94") (name "unconnected-(U9-SDO-Pad4)") (class "Default")
      (node (ref "U9") (pin "4") (pinfunction "SDO_4") (pintype "unspecified"))
    )
    (net (code "95") (name "unconnected-(USB1-EH-Pad6)") (class "Default")
      (node (ref "USB1") (pin "6") (pinfunction "EH_6") (pintype "input"))
    )
    (net (code "96") (name "unconnected-(USB1-ID-Pad4)") (class "Default")
      (node (ref "USB1") (pin "4") (pinfunction "ID_4") (pintype "input"))
    )
  )
)
